# 1GHz_Elektor_Probe.net
KiCad netlist of a schematic drawn in EAGLE
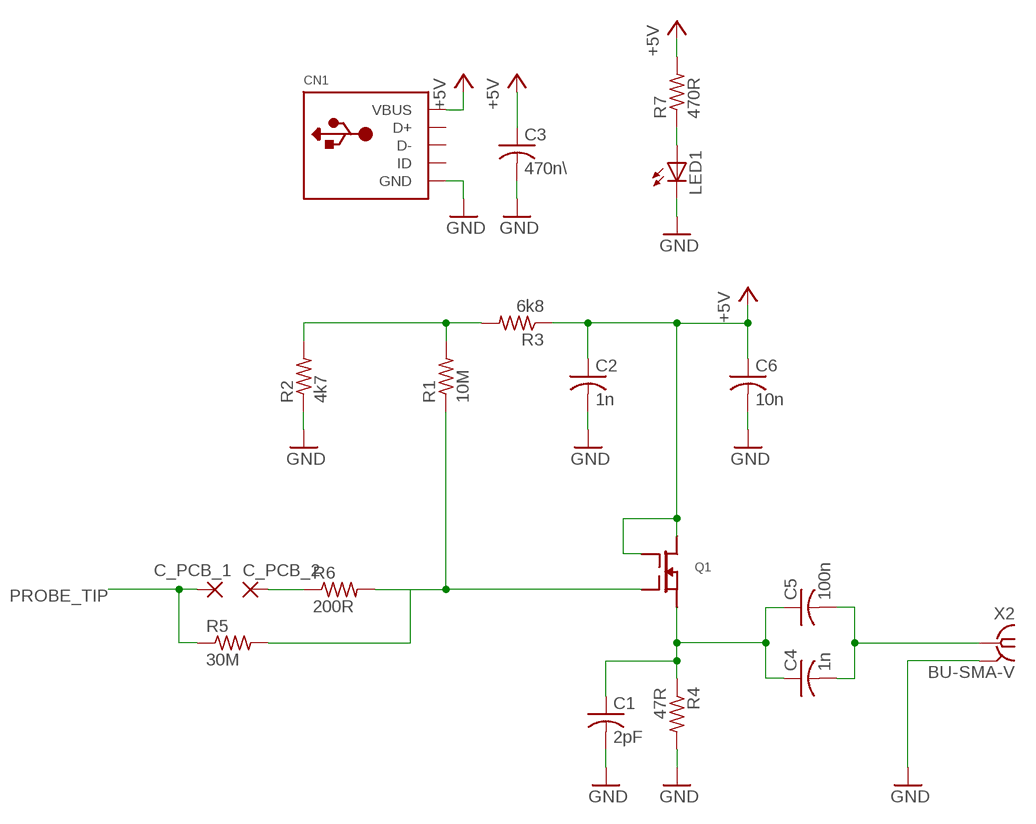
[diagram p0: schematic, sheet 1]

(export (version "E")
  (design (tool "Eeschema 10.0.6"))
  (components
    (comp (ref "C1")
      (value "2pF")
      (footprint "eagle-import:C0805")
      (libsource (lib "eagle-import") (part "C-USC0805"))
    )
    (comp (ref "C2")
      (value "1n")
      (footprint "eagle-import:C0805")
      (libsource (lib "eagle-import") (part "C-USC0805"))
    )
    (comp (ref "C3")
      (value "470n\\")
      (footprint "eagle-import:C0805")
      (libsource (lib "eagle-import") (part "C-USC0805"))
    )
    (comp (ref "C4")
      (value "1n")
      (footprint "eagle-import:C0805")
      (libsource (lib "eagle-import") (part "C-USC0805"))
    )
    (comp (ref "C5")
      (value "100n")
      (footprint "eagle-import:C0805")
      (libsource (lib "eagle-import") (part "C-USC0805"))
    )
    (comp (ref "C6")
      (value "10n")
      (footprint "eagle-import:C0805")
      (libsource (lib "eagle-import") (part "C-USC0805"))
    )
    (comp (ref "CN1")
      (value "USBMINIB")
      (footprint "eagle-import:USB-MINIB")
      (libsource (lib "eagle-import") (part "USBMINIB"))
    )
    (comp (ref "C_PCB_1")
      (value "SMD5")
      (footprint "eagle-import:SMD2,54-5,08")
      (libsource (lib "eagle-import") (part "SMD5"))
    )
    (comp (ref "C_PCB_2")
      (value "SMD5")
      (footprint "eagle-import:SMD2,54-5,08")
      (libsource (lib "eagle-import") (part "SMD5"))
    )
    (comp (ref "LED1")
      (value "LED3MM")
      (footprint "eagle-import:LED3MM")
      (libsource (lib "eagle-import") (part "LED3MM"))
    )
    (comp (ref "Q1")
      (value "BF998")
      (footprint "eagle-import:SOT143B")
      (libsource (lib "eagle-import") (part "BF998"))
    )
    (comp (ref "R1")
      (value "10M")
      (footprint "eagle-import:R0805")
      (libsource (lib "eagle-import") (part "R-US_R0805"))
    )
    (comp (ref "R2")
      (value "4k7")
      (footprint "eagle-import:R0805")
      (libsource (lib "eagle-import") (part "R-US_R0805"))
    )
    (comp (ref "R3")
      (value "6k8")
      (footprint "eagle-import:R0805")
      (libsource (lib "eagle-import") (part "R-US_R0805"))
    )
    (comp (ref "R4")
      (value "47R")
      (footprint "eagle-import:R0805")
      (libsource (lib "eagle-import") (part "R-US_R0805"))
    )
    (comp (ref "R5")
      (value "30M")
      (footprint "eagle-import:R0805")
      (libsource (lib "eagle-import") (part "R-US_R0805"))
    )
    (comp (ref "R6")
      (value "200R")
      (footprint "eagle-import:R0805")
      (libsource (lib "eagle-import") (part "R-US_R0805"))
    )
    (comp (ref "R7")
      (value "470R")
      (footprint "eagle-import:R0805")
      (libsource (lib "eagle-import") (part "R-US_R0805"))
    )
    (comp (ref "X2")
      (value "BU-SMA-V")
      (footprint "eagle-import:BU-SMA-V")
      (libsource (lib "eagle-import") (part "BU-SMA-V"))
    )
  )
  (nets
    (net (code "1") (name "+5V") (class "Default")
      (node (ref "C2") (pin "1") (pinfunction "1_1") (pintype "passive"))
      (node (ref "C3") (pin "1") (pinfunction "1_1") (pintype "passive"))
      (node (ref "C6") (pin "1") (pinfunction "1_1") (pintype "passive"))
      (node (ref "CN1") (pin "VBUS") (pinfunction "VBUS_VBUS") (pintype "power_in"))
      (node (ref "Q1") (pin "2") (pinfunction "D_2") (pintype "bidirectional"))
      (node (ref "Q1") (pin "3") (pinfunction "G2_3") (pintype "bidirectional"))
      (node (ref "R3") (pin "1") (pinfunction "1_1") (pintype "passive"))
      (node (ref "R7") (pin "2") (pinfunction "2_2") (pintype "passive"))
    )
    (net (code "2") (name "/PROBE_TIP") (class "Default")
      (node (ref "C_PCB_1") (pin "1") (pinfunction "P_1") (pintype "passive"))
      (node (ref "R5") (pin "1") (pinfunction "1_1") (pintype "passive"))
    )
    (net (code "3") (name "GND") (class "Default")
      (node (ref "C1") (pin "2") (pinfunction "2_2") (pintype "passive"))
      (node (ref "C2") (pin "2") (pinfunction "2_2") (pintype "passive"))
      (node (ref "C3") (pin "2") (pinfunction "2_2") (pintype "passive"))
      (node (ref "C6") (pin "2") (pinfunction "2_2") (pintype "passive"))
      (node (ref "CN1") (pin "GND") (pinfunction "GND_GND") (pintype "power_in"))
      (node (ref "LED1") (pin "K") (pinfunction "C_K") (pintype "passive"))
      (node (ref "R2") (pin "1") (pinfunction "1_1") (pintype "passive"))
      (node (ref "R4") (pin "2") (pinfunction "2_2") (pintype "passive"))
      (node (ref "X2") (pin "2") (pinfunction "GND_2") (pintype "power_in"))
    )
    (net (code "4") (name "Net-(C4-Pad2)") (class "Default")
      (node (ref "C4") (pin "2") (pinfunction "2_2") (pintype "passive"))
      (node (ref "C5") (pin "2") (pinfunction "2_2") (pintype "passive"))
      (node (ref "X2") (pin "1") (pinfunction "1_1") (pintype "passive"))
    )
    (net (code "5") (name "Net-(C_PCB_2-P)") (class "Default")
      (node (ref "C_PCB_2") (pin "1") (pinfunction "P_1") (pintype "passive"))
      (node (ref "R6") (pin "1") (pinfunction "1_1") (pintype "passive"))
    )
    (net (code "6") (name "Net-(LED1-PadA)") (class "Default")
      (node (ref "LED1") (pin "A") (pinfunction "A_A") (pintype "passive"))
      (node (ref "R7") (pin "1") (pinfunction "1_1") (pintype "passive"))
    )
    (net (code "7") (name "Net-(Q1-G1)") (class "Default")
      (node (ref "Q1") (pin "4") (pinfunction "G1_4") (pintype "bidirectional"))
      (node (ref "R1") (pin "1") (pinfunction "1_1") (pintype "passive"))
      (node (ref "R5") (pin "2") (pinfunction "2_2") (pintype "passive"))
      (node (ref "R6") (pin "2") (pinfunction "2_2") (pintype "passive"))
    )
    (net (code "8") (name "Net-(Q1-S)") (class "Default")
      (node (ref "C1") (pin "1") (pinfunction "1_1") (pintype "passive"))
      (node (ref "C4") (pin "1") (pinfunction "1_1") (pintype "passive"))
      (node (ref "C5") (pin "1") (pinfunction "1_1") (pintype "passive"))
      (node (ref "Q1") (pin "1") (pinfunction "S_1") (pintype "bidirectional"))
      (node (ref "R4") (pin "1") (pinfunction "1_1") (pintype "passive"))
    )
    (net (code "9") (name "Net-(R1-Pad2)") (class "Default")
      (node (ref "R1") (pin "2") (pinfunction "2_2") (pintype "passive"))
      (node (ref "R2") (pin "2") (pinfunction "2_2") (pintype "passive"))
      (node (ref "R3") (pin "2") (pinfunction "2_2") (pintype "passive"))
    )
    (net (code "10") (name "unconnected-(CN1-PadD+)") (class "Default")
      (node (ref "CN1") (pin "D+") (pinfunction "D+_D+") (pintype "bidirectional"))
    )
    (net (code "11") (name "unconnected-(CN1-PadD-)") (class "Default")
      (node (ref "CN1") (pin "D-") (pinfunction "D-_D-") (pintype "bidirectional"))
    )
    (net (code "12") (name "unconnected-(CN1-PadID)") (class "Default")
      (node (ref "CN1") (pin "ID") (pinfunction "ID_ID") (pintype "bidirectional"))
    )
  )
)
